# Schematic.net
KiCad netlist of a schematic drawn in EAGLE
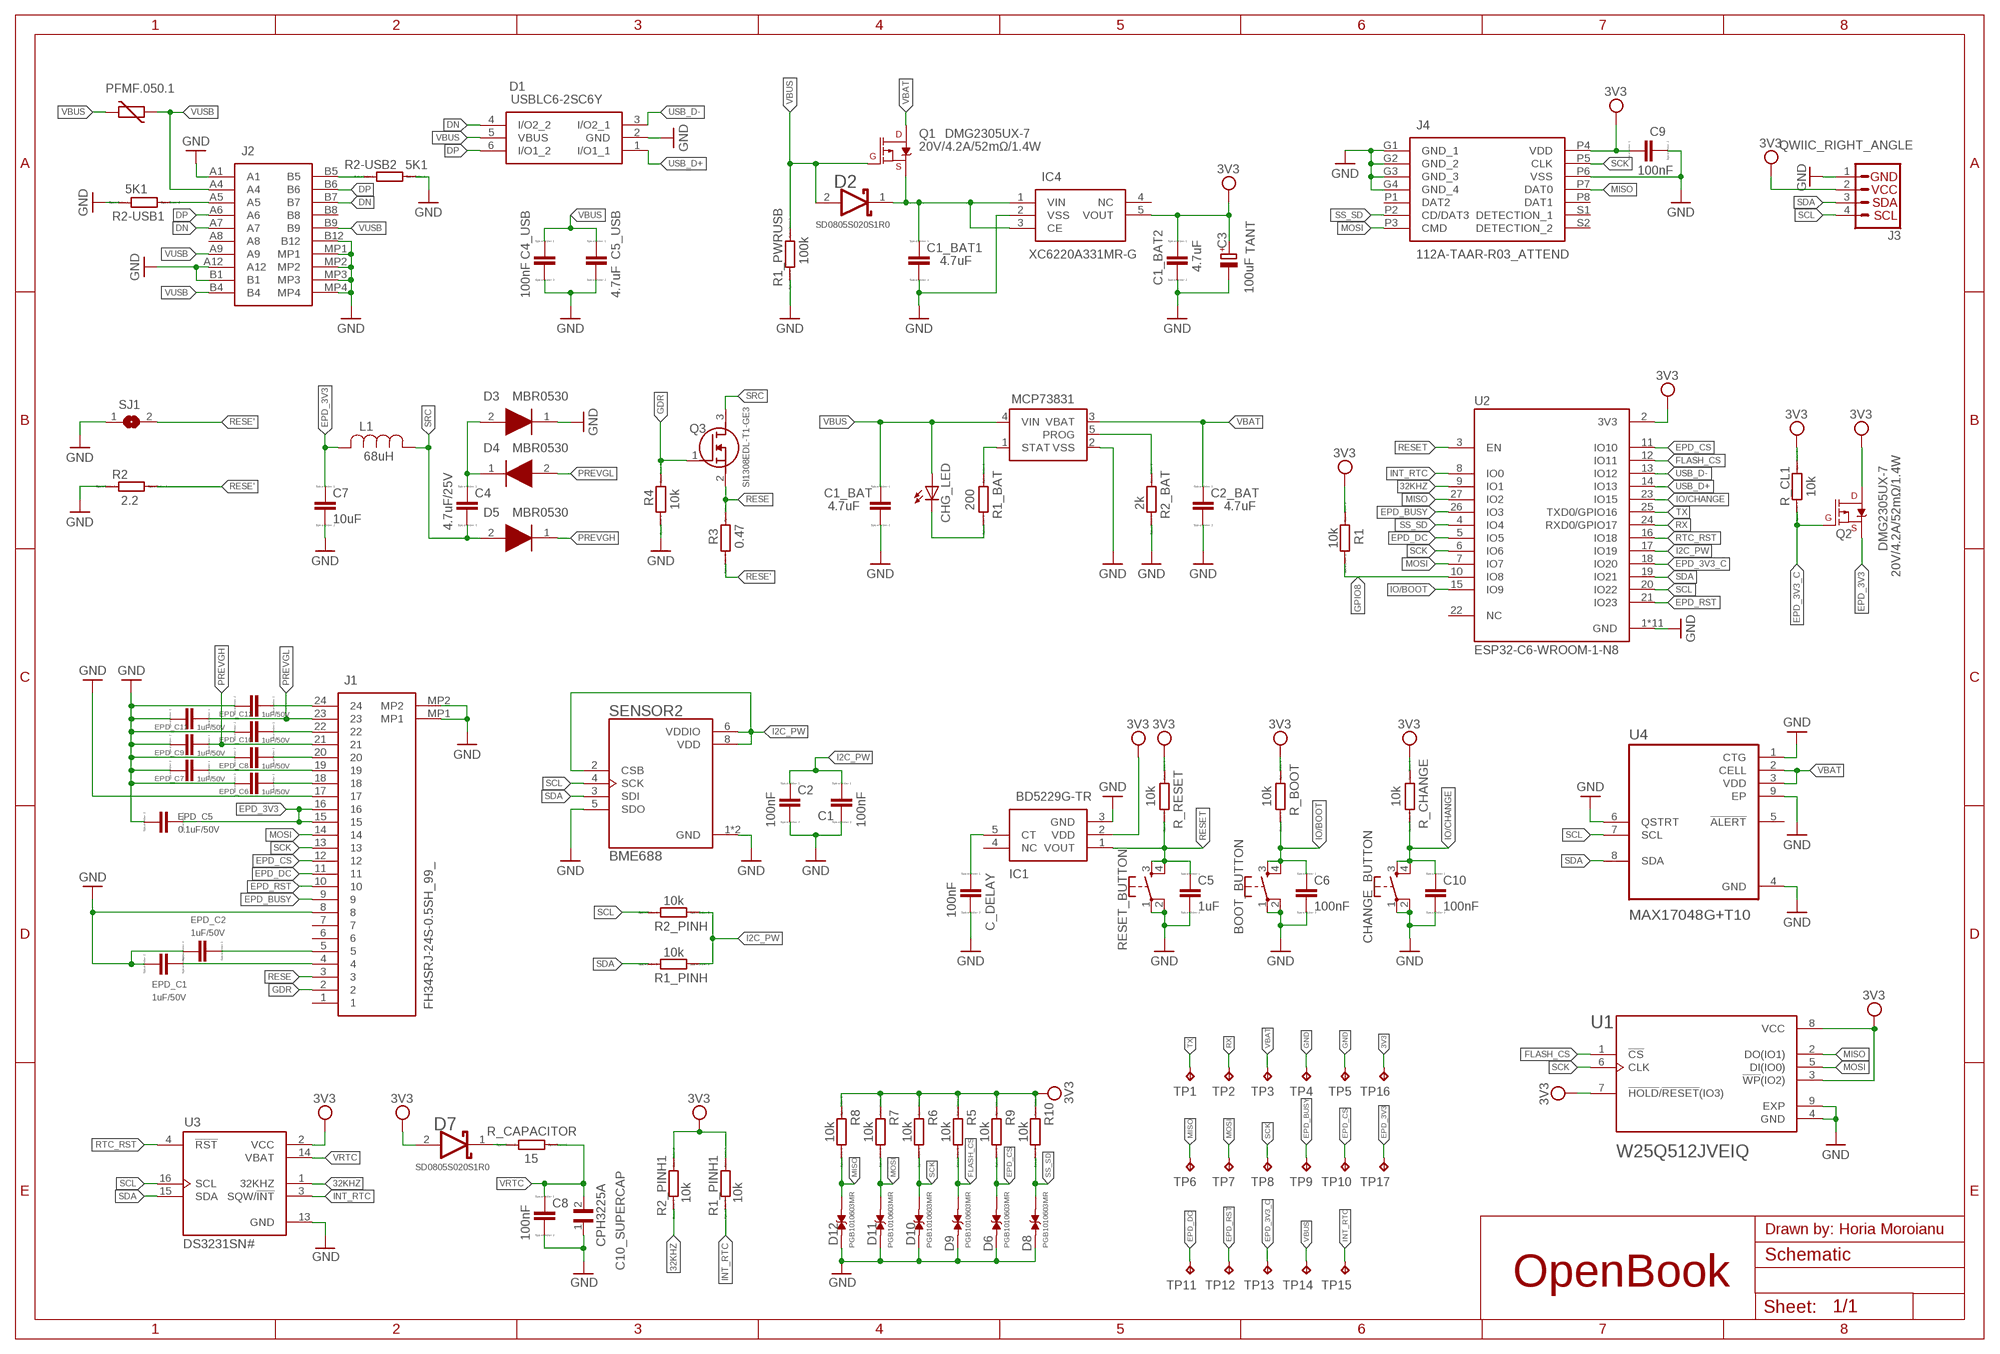
[diagram p0: schematic, sheet 1]

(export (version "E")
  (design (tool "Eeschema 10.0.6"))
  (components
    (comp (ref "BOOT_BUTTON")
      (value "BUTTON_CUSYOMV1")
      (footprint "eagle-import:MYBUTTON")
      (libsource (lib "eagle-import") (part "BUTTON_CUSYOMV1"))
    )
    (comp (ref "C1")
      (value "100nF")
      (footprint "eagle-import:EAGLE-LTSPICE_C0402")
      (libsource (lib "eagle-import") (part "EAGLE-LTSPICE_CC0402"))
    )
    (comp (ref "C1_BAT")
      (value "4.7uF")
      (footprint "eagle-import:EAGLE-LTSPICE_C0402")
      (libsource (lib "eagle-import") (part "EAGLE-LTSPICE_CC0402"))
    )
    (comp (ref "C1_BAT1")
      (value "4.7uF")
      (footprint "eagle-import:EAGLE-LTSPICE_C0402")
      (libsource (lib "eagle-import") (part "EAGLE-LTSPICE_CC0402"))
    )
    (comp (ref "C1_BAT2")
      (value "4.7uF")
      (footprint "eagle-import:EAGLE-LTSPICE_C0402")
      (libsource (lib "eagle-import") (part "EAGLE-LTSPICE_CC0402"))
    )
    (comp (ref "C2")
      (value "100nF")
      (footprint "eagle-import:EAGLE-LTSPICE_C0402")
      (libsource (lib "eagle-import") (part "EAGLE-LTSPICE_CC0402"))
    )
    (comp (ref "C2_BAT")
      (value "4.7uF")
      (footprint "eagle-import:EAGLE-LTSPICE_C0402")
      (libsource (lib "eagle-import") (part "EAGLE-LTSPICE_CC0402"))
    )
    (comp (ref "C3")
      (value "100uF")
      (footprint "eagle-import:RCL_CT3528")
      (libsource (lib "eagle-import") (part "RCL_CPOL-EUCT3528"))
    )
    (comp (ref "C4")
      (value "4.7uF/25V")
      (footprint "eagle-import:EAGLE-LTSPICE_C0402")
      (libsource (lib "eagle-import") (part "EAGLE-LTSPICE_CC0402"))
    )
    (comp (ref "C4_USB")
      (value "100nF")
      (footprint "eagle-import:EAGLE-LTSPICE_C0402")
      (libsource (lib "eagle-import") (part "EAGLE-LTSPICE_CC0402"))
    )
    (comp (ref "C5")
      (value "1uF")
      (footprint "eagle-import:EAGLE-LTSPICE_C0402")
      (libsource (lib "eagle-import") (part "EAGLE-LTSPICE_CC0402"))
    )
    (comp (ref "C5_USB")
      (value "4.7uF")
      (footprint "eagle-import:EAGLE-LTSPICE_C0402")
      (libsource (lib "eagle-import") (part "EAGLE-LTSPICE_CC0402"))
    )
    (comp (ref "C6")
      (value "100nF")
      (footprint "eagle-import:EAGLE-LTSPICE_C0402")
      (libsource (lib "eagle-import") (part "EAGLE-LTSPICE_CC0402"))
    )
    (comp (ref "C7")
      (value "10uF")
      (footprint "eagle-import:EAGLE-LTSPICE_C0402")
      (libsource (lib "eagle-import") (part "EAGLE-LTSPICE_CC0402"))
    )
    (comp (ref "C8")
      (value "100nF")
      (footprint "eagle-import:EAGLE-LTSPICE_C0402")
      (libsource (lib "eagle-import") (part "EAGLE-LTSPICE_CC0402"))
    )
    (comp (ref "C9")
      (value "100nF")
      (footprint "eagle-import:EAGLE-LTSPICE_C0402")
      (libsource (lib "eagle-import") (part "EAGLE-LTSPICE_CC0402"))
    )
    (comp (ref "C10")
      (value "100nF")
      (footprint "eagle-import:EAGLE-LTSPICE_C0402")
      (libsource (lib "eagle-import") (part "EAGLE-LTSPICE_CC0402"))
    )
    (comp (ref "C10_SUPERCAP")
      (value "CPH3225A")
      (footprint "eagle-import:CAPCP3225X100N")
      (fields (field (name "MF") "Seiko Instruments"))
      (libsource (lib "eagle-import") (part "CPH3225A"))
    )
    (comp (ref "CHANGE_BUTTON")
      (value "BUTTON_CUSYOMV1")
      (footprint "eagle-import:MYBUTTON")
      (libsource (lib "eagle-import") (part "BUTTON_CUSYOMV1"))
    )
    (comp (ref "CHG_LED")
      (value "ADAFRUIT_LEDCHIP-LED0603")
      (footprint "eagle-import:ADAFRUIT_CHIP-LED0603")
      (libsource (lib "eagle-import") (part "ADAFRUIT_LEDCHIP-LED0603"))
    )
    (comp (ref "C_DELAY")
      (value "100nF")
      (footprint "eagle-import:EAGLE-LTSPICE_C0402")
      (libsource (lib "eagle-import") (part "EAGLE-LTSPICE_CC0402"))
    )
    (comp (ref "D1")
      (value "USBLC6-2SC6Y")
      (footprint "eagle-import:SOT95P280X145-6N")
      (fields (field (name "MF") "STMicroelectronics"))
      (libsource (lib "eagle-import") (part "USBLC6-2SC6Y"))
    )
    (comp (ref "D2")
      (value "ESP32_WROVER_AVX---SD0805S020S1R0_AVX_SD0805S020S1R0_0_0AVX_SD0805S020S1R0_0_0")
      (footprint "eagle-import:ESP32_WROVER_AVX---SD0805S020S1R0_AVX_SD0805S020S1R0_0")
      (fields
        (field (name "DIGIKEY_PART_NUMBER") "478-7800-1-ND")
        (field (name "MF") "AVX")
        (field (name "MOUSER_PART_NUMBER") "581-SD0805S020S1R0")
      )
      (libsource (lib "eagle-import") (part "ESP32_WROVER_AVX---SD0805S020S1R0_AVX_SD0805S020S1R0_0_0AVX_SD0805S020S1R0_0_0"))
    )
    (comp (ref "D3")
      (value "MBR0530")
      (footprint "eagle-import:SOD3716X135N")
      (fields (field (name "MF") "ON Semiconductor"))
      (libsource (lib "eagle-import") (part "MBR0530"))
    )
    (comp (ref "D4")
      (value "MBR0530")
      (footprint "eagle-import:SOD3716X135N")
      (fields (field (name "MF") "ON Semiconductor"))
      (libsource (lib "eagle-import") (part "MBR0530"))
    )
    (comp (ref "D5")
      (value "MBR0530")
      (footprint "eagle-import:SOD3716X135N")
      (fields (field (name "MF") "ON Semiconductor"))
      (libsource (lib "eagle-import") (part "MBR0530"))
    )
    (comp (ref "D6")
      (value "PGB1010603MR")
      (footprint "eagle-import:DIOC1608X36N")
      (fields (field (name "MF") "Littelfuse Inc."))
      (libsource (lib "eagle-import") (part "PGB1010603MR"))
    )
    (comp (ref "D7")
      (value "ESP32_WROVER_AVX---SD0805S020S1R0_AVX_SD0805S020S1R0_0_0AVX_SD0805S020S1R0_0_0")
      (footprint "eagle-import:ESP32_WROVER_AVX---SD0805S020S1R0_AVX_SD0805S020S1R0_0")
      (fields
        (field (name "DIGIKEY_PART_NUMBER") "478-7800-1-ND")
        (field (name "MF") "AVX")
        (field (name "MOUSER_PART_NUMBER") "581-SD0805S020S1R0")
      )
      (libsource (lib "eagle-import") (part "ESP32_WROVER_AVX---SD0805S020S1R0_AVX_SD0805S020S1R0_0_0AVX_SD0805S020S1R0_0_0"))
    )
    (comp (ref "D8")
      (value "PGB1010603MR")
      (footprint "eagle-import:DIOC1608X36N")
      (fields (field (name "MF") "Littelfuse Inc."))
      (libsource (lib "eagle-import") (part "PGB1010603MR"))
    )
    (comp (ref "D9")
      (value "PGB1010603MR")
      (footprint "eagle-import:DIOC1608X36N")
      (fields (field (name "MF") "Littelfuse Inc."))
      (libsource (lib "eagle-import") (part "PGB1010603MR"))
    )
    (comp (ref "D10")
      (value "PGB1010603MR")
      (footprint "eagle-import:DIOC1608X36N")
      (fields (field (name "MF") "Littelfuse Inc."))
      (libsource (lib "eagle-import") (part "PGB1010603MR"))
    )
    (comp (ref "D11")
      (value "PGB1010603MR")
      (footprint "eagle-import:DIOC1608X36N")
      (fields (field (name "MF") "Littelfuse Inc."))
      (libsource (lib "eagle-import") (part "PGB1010603MR"))
    )
    (comp (ref "D12")
      (value "PGB1010603MR")
      (footprint "eagle-import:DIOC1608X36N")
      (fields (field (name "MF") "Littelfuse Inc."))
      (libsource (lib "eagle-import") (part "PGB1010603MR"))
    )
    (comp (ref "EPD_C1")
      (value "1uF/50V")
      (footprint "eagle-import:EAGLE-LTSPICE_C0402")
      (libsource (lib "eagle-import") (part "EAGLE-LTSPICE_CC0402"))
    )
    (comp (ref "EPD_C2")
      (value "1uF/50V")
      (footprint "eagle-import:EAGLE-LTSPICE_C0402")
      (libsource (lib "eagle-import") (part "EAGLE-LTSPICE_CC0402"))
    )
    (comp (ref "EPD_C5")
      (value "0.1uF/50V")
      (footprint "eagle-import:EAGLE-LTSPICE_C0402")
      (libsource (lib "eagle-import") (part "EAGLE-LTSPICE_CC0402"))
    )
    (comp (ref "EPD_C6")
      (value "1uF/50V")
      (footprint "eagle-import:EAGLE-LTSPICE_C0402")
      (libsource (lib "eagle-import") (part "EAGLE-LTSPICE_CC0402"))
    )
    (comp (ref "EPD_C7")
      (value "1uF/50V")
      (footprint "eagle-import:EAGLE-LTSPICE_C0402")
      (libsource (lib "eagle-import") (part "EAGLE-LTSPICE_CC0402"))
    )
    (comp (ref "EPD_C8")
      (value "1uF/50V")
      (footprint "eagle-import:EAGLE-LTSPICE_C0402")
      (libsource (lib "eagle-import") (part "EAGLE-LTSPICE_CC0402"))
    )
    (comp (ref "EPD_C9")
      (value "1uF/50V")
      (footprint "eagle-import:EAGLE-LTSPICE_C0402")
      (libsource (lib "eagle-import") (part "EAGLE-LTSPICE_CC0402"))
    )
    (comp (ref "EPD_C10")
      (value "1uF/50V")
      (footprint "eagle-import:EAGLE-LTSPICE_C0402")
      (libsource (lib "eagle-import") (part "EAGLE-LTSPICE_CC0402"))
    )
    (comp (ref "EPD_C11")
      (value "1uF/50V")
      (footprint "eagle-import:EAGLE-LTSPICE_C0402")
      (libsource (lib "eagle-import") (part "EAGLE-LTSPICE_CC0402"))
    )
    (comp (ref "EPD_C12")
      (value "1uF/50V")
      (footprint "eagle-import:EAGLE-LTSPICE_C0402")
      (libsource (lib "eagle-import") (part "EAGLE-LTSPICE_CC0402"))
    )
    (comp (ref "IC1")
      (value "BD5229G-TR")
      (footprint "eagle-import:SOT95P280X125-5N")
      (fields (field (name "MOUSER_PART_NUMBER") "755-BD5229G-TR"))
      (libsource (lib "eagle-import") (part "BD5229G-TR"))
    )
    (comp (ref "IC4")
      (value "XC6220A331MR-G")
      (footprint "eagle-import:SOT95P280X120-5N")
      (fields (field (name "MOUSER_PART_NUMBER") "865-XC6220A331MR-G"))
      (libsource (lib "eagle-import") (part "XC6220A331MR-G"))
    )
    (comp (ref "J1")
      (value "FH34SRJ-24S-0.5SH_99_")
      (footprint "eagle-import:FH34SRJ24S05SH99")
      (fields
        (field (name "MANUFACTURER_PART_NUMBER") "FH34SRJ-24S-0.5SH(99)")
        (field (name "MOUSER_PART_NUMBER") "798-FH34SRJ24S05SH99")
      )
      (libsource (lib "eagle-import") (part "FH34SRJ-24S-0.5SH_99_"))
    )
    (comp (ref "J2")
      (value "SAMACSYS_PARTS_USB4110-GF-A")
      (footprint "eagle-import:SAMACSYS_PARTS_USB4110GFA")
      (fields
        (field (name "MANUFACTURER_PART_NUMBER") "USB4110-GF-A")
        (field (name "MOUSER_PART_NUMBER") "640-USB4110-GF-A")
      )
      (libsource (lib "eagle-import") (part "SAMACSYS_PARTS_USB4110-GF-A"))
    )
    (comp (ref "J3")
      (value "QWIIC_RIGHT_ANGLE")
      (footprint "eagle-import:JST04_1MM_RA")
      (libsource (lib "eagle-import") (part "QWIIC_CONNECTORJS-1MM"))
    )
    (comp (ref "J4")
      (value "112A-TAAR-R03_ATTEND")
      (footprint "eagle-import:112ATAARR03ATTEND")
      (fields (field (name "MANUFACTURER_PART_NUMBER") "112A-TAAR-R03 ATTEND"))
      (libsource (lib "eagle-import") (part "112A-TAAR-R03_ATTEND"))
    )
    (comp (ref "L1")
      (value "744043680IND_4828-WE-TPC_WRE")
      (footprint "eagle-import:IND_4828-WE-TPC_WRE")
      (fields
        (field (name "MANUFACTURER_PART_NUMBER") "744043680")
        (field (name "VAL") "68uH")
        (field (name "COPYRIGHT") "Copyright (C) 2024 Ultra Librarian. All rights reserved.")
      )
      (libsource (lib "eagle-import") (part "744043680IND_4828-WE-TPC_WRE"))
    )
    (comp (ref "PFMF.050.1")
      (value "ESP32C6_VARISTORCN1812")
      (footprint "eagle-import:ESP32C6_VARISTOR_CT_CN1812")
      (libsource (lib "eagle-import") (part "ESP32C6_VARISTORCN1812"))
    )
    (comp (ref "Q1")
      (value "20V/4.2A/52mΩ/1.4W")
      (footprint "eagle-import:ESP32_WROVER_SPARKFUN-DISCRETESEMI_SOT23-3")
      (libsource (lib "eagle-import") (part "ESP32_WROVER_SPARKFUN-DISCRETESEMI_MOSFET_PCH-DMG2305UX-7"))
    )
    (comp (ref "Q2")
      (value "20V/4.2A/52mΩ/1.4W")
      (footprint "eagle-import:ESP32_WROVER_SPARKFUN-DISCRETESEMI_SOT23-3")
      (libsource (lib "eagle-import") (part "ESP32_WROVER_SPARKFUN-DISCRETESEMI_MOSFET_PCH-DMG2305UX-7"))
    )
    (comp (ref "Q3")
      (value "SI1308EDL-T1-GE3")
      (footprint "eagle-import:SOT65P210X110-3N")
      (fields (field (name "MF") "Vishay Siliconix"))
      (libsource (lib "eagle-import") (part "SI1308EDL-T1-GE3"))
    )
    (comp (ref "R1")
      (value "10k")
      (footprint "eagle-import:ESP32_WROVER_EAGLE-LTSPICE_R0402")
      (libsource (lib "eagle-import") (part "ESP32_WROVER_EAGLE-LTSPICE_RR0402"))
    )
    (comp (ref "R1_BAT")
      (value "200")
      (footprint "eagle-import:ESP32_WROVER_EAGLE-LTSPICE_R0402")
      (libsource (lib "eagle-import") (part "ESP32_WROVER_EAGLE-LTSPICE_RR0402"))
    )
    (comp (ref "R1_PINH")
      (value "10k")
      (footprint "eagle-import:ESP32_WROVER_EAGLE-LTSPICE_R0402")
      (libsource (lib "eagle-import") (part "ESP32_WROVER_EAGLE-LTSPICE_RR0402"))
    )
    (comp (ref "R1_PINH1")
      (value "10k")
      (footprint "eagle-import:ESP32_WROVER_EAGLE-LTSPICE_R0402")
      (libsource (lib "eagle-import") (part "ESP32_WROVER_EAGLE-LTSPICE_RR0402"))
    )
    (comp (ref "R1_PWRUSB")
      (value "100k")
      (footprint "eagle-import:ESP32_WROVER_EAGLE-LTSPICE_R0402")
      (libsource (lib "eagle-import") (part "ESP32_WROVER_EAGLE-LTSPICE_RR0402"))
    )
    (comp (ref "R2")
      (value "2.2")
      (footprint "eagle-import:ESP32_WROVER_EAGLE-LTSPICE_R0402")
      (libsource (lib "eagle-import") (part "ESP32_WROVER_EAGLE-LTSPICE_RR0402"))
    )
    (comp (ref "R2-USB1")
      (value "5K1")
      (footprint "eagle-import:ESP32_WROVER_EAGLE-LTSPICE_R0402")
      (libsource (lib "eagle-import") (part "ESP32_WROVER_EAGLE-LTSPICE_RR0402"))
    )
    (comp (ref "R2-USB2")
      (value "5K1")
      (footprint "eagle-import:ESP32_WROVER_EAGLE-LTSPICE_R0402")
      (libsource (lib "eagle-import") (part "ESP32_WROVER_EAGLE-LTSPICE_RR0402"))
    )
    (comp (ref "R2_BAT")
      (value "2k")
      (footprint "eagle-import:ESP32_WROVER_EAGLE-LTSPICE_R0402")
      (libsource (lib "eagle-import") (part "ESP32_WROVER_EAGLE-LTSPICE_RR0402"))
    )
    (comp (ref "R2_PINH")
      (value "10k")
      (footprint "eagle-import:ESP32_WROVER_EAGLE-LTSPICE_R0402")
      (libsource (lib "eagle-import") (part "ESP32_WROVER_EAGLE-LTSPICE_RR0402"))
    )
    (comp (ref "R2_PINH1")
      (value "10k")
      (footprint "eagle-import:ESP32_WROVER_EAGLE-LTSPICE_R0402")
      (libsource (lib "eagle-import") (part "ESP32_WROVER_EAGLE-LTSPICE_RR0402"))
    )
    (comp (ref "R3")
      (value "0.47")
      (footprint "eagle-import:ESP32_WROVER_EAGLE-LTSPICE_R0402")
      (libsource (lib "eagle-import") (part "ESP32_WROVER_EAGLE-LTSPICE_RR0402"))
    )
    (comp (ref "R4")
      (value "10k")
      (footprint "eagle-import:ESP32_WROVER_EAGLE-LTSPICE_R0402")
      (libsource (lib "eagle-import") (part "ESP32_WROVER_EAGLE-LTSPICE_RR0402"))
    )
    (comp (ref "R5")
      (value "10k")
      (footprint "eagle-import:ESP32_WROVER_EAGLE-LTSPICE_R0402")
      (libsource (lib "eagle-import") (part "ESP32_WROVER_EAGLE-LTSPICE_RR0402"))
    )
    (comp (ref "R6")
      (value "10k")
      (footprint "eagle-import:ESP32_WROVER_EAGLE-LTSPICE_R0402")
      (libsource (lib "eagle-import") (part "ESP32_WROVER_EAGLE-LTSPICE_RR0402"))
    )
    (comp (ref "R7")
      (value "10k")
      (footprint "eagle-import:ESP32_WROVER_EAGLE-LTSPICE_R0402")
      (libsource (lib "eagle-import") (part "ESP32_WROVER_EAGLE-LTSPICE_RR0402"))
    )
    (comp (ref "R8")
      (value "10k")
      (footprint "eagle-import:ESP32_WROVER_EAGLE-LTSPICE_R0402")
      (libsource (lib "eagle-import") (part "ESP32_WROVER_EAGLE-LTSPICE_RR0402"))
    )
    (comp (ref "R9")
      (value "10k")
      (footprint "eagle-import:ESP32_WROVER_EAGLE-LTSPICE_R0402")
      (libsource (lib "eagle-import") (part "ESP32_WROVER_EAGLE-LTSPICE_RR0402"))
    )
    (comp (ref "R10")
      (value "10k")
      (footprint "eagle-import:ESP32_WROVER_EAGLE-LTSPICE_R0402")
      (libsource (lib "eagle-import") (part "ESP32_WROVER_EAGLE-LTSPICE_RR0402"))
    )
    (comp (ref "RESET_BUTTON")
      (value "BUTTON_CUSYOMV1")
      (footprint "eagle-import:MYBUTTON")
      (libsource (lib "eagle-import") (part "BUTTON_CUSYOMV1"))
    )
    (comp (ref "R_BOOT")
      (value "10k")
      (footprint "eagle-import:ESP32_WROVER_EAGLE-LTSPICE_R0402")
      (libsource (lib "eagle-import") (part "ESP32_WROVER_EAGLE-LTSPICE_RR0402"))
    )
    (comp (ref "R_CAPACITOR")
      (value "15")
      (footprint "eagle-import:ESP32_WROVER_EAGLE-LTSPICE_R0402")
      (libsource (lib "eagle-import") (part "ESP32_WROVER_EAGLE-LTSPICE_RR0402"))
    )
    (comp (ref "R_CHANGE")
      (value "10k")
      (footprint "eagle-import:ESP32_WROVER_EAGLE-LTSPICE_R0402")
      (libsource (lib "eagle-import") (part "ESP32_WROVER_EAGLE-LTSPICE_RR0402"))
    )
    (comp (ref "R_CL1")
      (value "10k")
      (footprint "eagle-import:ESP32_WROVER_EAGLE-LTSPICE_R0402")
      (libsource (lib "eagle-import") (part "ESP32_WROVER_EAGLE-LTSPICE_RR0402"))
    )
    (comp (ref "R_RESET")
      (value "10k")
      (footprint "eagle-import:ESP32_WROVER_EAGLE-LTSPICE_R0402")
      (libsource (lib "eagle-import") (part "ESP32_WROVER_EAGLE-LTSPICE_RR0402"))
    )
    (comp (ref "SENSOR2")
      (value "ESP32_WROVER_BME680_BME680")
      (footprint "eagle-import:ESP32_WROVER_BME680_PSON80P300X300X100-8N")
      (fields (field (name "MF") "Bosch Sensortec") (field (name "MP") "BME680"))
      (libsource (lib "eagle-import") (part "ESP32_WROVER_BME680_BME680"))
    )
    (comp (ref "SJ1") (value "SJ") (footprint "eagle-import:SJ") (libsource (lib "eagle-import") (part "SJ")))
    (comp (ref "TP1")
      (value "TPTP20R")
      (footprint "eagle-import:TP20R")
      (libsource (lib "eagle-import") (part "TPTP20R"))
    )
    (comp (ref "TP2")
      (value "TPTP20R")
      (footprint "eagle-import:TP20R")
      (libsource (lib "eagle-import") (part "TPTP20R"))
    )
    (comp (ref "TP3")
      (value "TPTP20R")
      (footprint "eagle-import:TP20R")
      (libsource (lib "eagle-import") (part "TPTP20R"))
    )
    (comp (ref "TP4")
      (value "TPTP20R")
      (footprint "eagle-import:TP20R")
      (libsource (lib "eagle-import") (part "TPTP20R"))
    )
    (comp (ref "TP5")
      (value "TPTP20R")
      (footprint "eagle-import:TP20R")
      (libsource (lib "eagle-import") (part "TPTP20R"))
    )
    (comp (ref "TP6")
      (value "TPTP20R")
      (footprint "eagle-import:TP20R")
      (libsource (lib "eagle-import") (part "TPTP20R"))
    )
    (comp (ref "TP7")
      (value "TPTP20R")
      (footprint "eagle-import:TP20R")
      (libsource (lib "eagle-import") (part "TPTP20R"))
    )
    (comp (ref "TP8")
      (value "TPTP20R")
      (footprint "eagle-import:TP20R")
      (libsource (lib "eagle-import") (part "TPTP20R"))
    )
    (comp (ref "TP9")
      (value "TPTP20R")
      (footprint "eagle-import:TP20R")
      (libsource (lib "eagle-import") (part "TPTP20R"))
    )
    (comp (ref "TP10")
      (value "TPTP20R")
      (footprint "eagle-import:TP20R")
      (libsource (lib "eagle-import") (part "TPTP20R"))
    )
    (comp (ref "TP11")
      (value "TPTP20R")
      (footprint "eagle-import:TP20R")
      (libsource (lib "eagle-import") (part "TPTP20R"))
    )
    (comp (ref "TP12")
      (value "TPTP20R")
      (footprint "eagle-import:TP20R")
      (libsource (lib "eagle-import") (part "TPTP20R"))
    )
    (comp (ref "TP13")
      (value "TPTP20R")
      (footprint "eagle-import:TP20R")
      (libsource (lib "eagle-import") (part "TPTP20R"))
    )
    (comp (ref "TP14")
      (value "TPTP20R")
      (footprint "eagle-import:TP20R")
      (libsource (lib "eagle-import") (part "TPTP20R"))
    )
    (comp (ref "TP15")
      (value "TPTP20R")
      (footprint "eagle-import:TP20R")
      (libsource (lib "eagle-import") (part "TPTP20R"))
    )
    (comp (ref "TP16")
      (value "TPTP20R")
      (footprint "eagle-import:TP20R")
      (libsource (lib "eagle-import") (part "TPTP20R"))
    )
    (comp (ref "TP17")
      (value "TPTP20R")
      (footprint "eagle-import:TP20R")
      (libsource (lib "eagle-import") (part "TPTP20R"))
    )
    (comp (ref "U1")
      (value "W25Q512JVEIQ")
      (footprint "eagle-import:SON127P600X800X80-9N")
      (fields (field (name "MF") "Winbond Electronics"))
      (libsource (lib "eagle-import") (part "W25Q512JVEIQ"))
    )
    (comp (ref "U2")
      (value "ESP32-C6-WROOM-1-N8")
      (footprint "eagle-import:XCVR_ESP32-C6-WROOM-1-N8")
      (fields (field (name "MF") "Espressif Systems"))
      (libsource (lib "eagle-import") (part "ESP32-C6-WROOM-1-N8"))
    )
    (comp (ref "U3")
      (value "DS3231SN#")
      (footprint "eagle-import:SOIC127P1032X265-16N")
      (fields (field (name "MF") "Analog Devices"))
      (libsource (lib "eagle-import") (part "DS3231SN#"))
    )
    (comp (ref "U4")
      (value "MAX17048G+T10")
      (footprint "eagle-import:SON50P200X200X80-9N")
      (fields (field (name "MF") "Analog Devices"))
      (libsource (lib "eagle-import") (part "MAX17048G+T10"))
    )
    (comp (ref "U5")
      (value "ESP32_WROVER_SPARKFUN-IC-POWER_MCP73831")
      (footprint "eagle-import:ESP32_WROVER_SPARKFUN-IC-POWER_SOT23-5")
      (libsource (lib "eagle-import") (part "ESP32_WROVER_SPARKFUN-IC-POWER_MCP73831"))
    )
  )
  (nets
    (net (code "1") (name "3V3") (class "Default")
      (node (ref "C1_BAT2") (pin "1") (pinfunction "1_1") (pintype "passive"))
      (node (ref "C3") (pin "+") (pinfunction "+_+") (pintype "passive"))
      (node (ref "C9") (pin "1") (pinfunction "1_1") (pintype "passive"))
      (node (ref "D7") (pin "2") (pinfunction "ANODE_2") (pintype "bidirectional"))
      (node (ref "IC1") (pin "2") (pinfunction "VDD_2") (pintype "bidirectional"))
      (node (ref "IC4") (pin "5") (pinfunction "VOUT_5") (pintype "bidirectional"))
      (node (ref "J3") (pin "2") (pinfunction "2_2") (pintype "power_in"))
      (node (ref "J4") (pin "P4") (pinfunction "VDD_P4") (pintype "bidirectional"))
      (node (ref "Q2") (pin "3") (pinfunction "D_3") (pintype "bidirectional"))
      (node (ref "R1") (pin "2") (pinfunction "2_2") (pintype "passive"))
      (node (ref "R10") (pin "2") (pinfunction "2_2") (pintype "passive"))
      (node (ref "R1_PINH1") (pin "2") (pinfunction "2_2") (pintype "passive"))
      (node (ref "R2_PINH1") (pin "2") (pinfunction "2_2") (pintype "passive"))
      (node (ref "R5") (pin "2") (pinfunction "2_2") (pintype "passive"))
      (node (ref "R6") (pin "2") (pinfunction "2_2") (pintype "passive"))
      (node (ref "R7") (pin "2") (pinfunction "2_2") (pintype "passive"))
      (node (ref "R8") (pin "2") (pinfunction "2_2") (pintype "passive"))
      (node (ref "R9") (pin "2") (pinfunction "2_2") (pintype "passive"))
      (node (ref "R_BOOT") (pin "1") (pinfunction "1_1") (pintype "passive"))
      (node (ref "R_CHANGE") (pin "1") (pinfunction "1_1") (pintype "passive"))
      (node (ref "R_CL1") (pin "2") (pinfunction "2_2") (pintype "passive"))
      (node (ref "R_RESET") (pin "1") (pinfunction "1_1") (pintype "passive"))
      (node (ref "TP16") (pin "TP") (pinfunction "TP_TP") (pintype "input"))
      (node (ref "U1") (pin "3") (pinfunction "~{WP}(IO2)_3") (pintype "bidirectional"))
      (node (ref "U1") (pin "7") (pinfunction "~{HOLD}/~{RESET}(IO3)_7") (pintype "bidirectional"))
      (node (ref "U1") (pin "8") (pinfunction "VCC_8") (pintype "power_in"))
      (node (ref "U2") (pin "2") (pinfunction "3V3_2") (pintype "power_in"))
      (node (ref "U3") (pin "2") (pinfunction "VCC_2") (pintype "power_in"))
    )
    (net (code "2") (name "32KHZ") (class "Default")
      (node (ref "R2_PINH1") (pin "1") (pinfunction "1_1") (pintype "passive"))
      (node (ref "U2") (pin "9") (pinfunction "IO1_9") (pintype "bidirectional"))
      (node (ref "U3") (pin "1") (pinfunction "32KHZ_1") (pintype "output"))
    )
    (net (code "3") (name "DN") (class "Default")
      (node (ref "D1") (pin "4") (pinfunction "I/O2_2_4") (pintype "bidirectional"))
      (node (ref "J2") (pin "A7") (pinfunction "A7_A7") (pintype "bidirectional"))
      (node (ref "J2") (pin "B7") (pinfunction "B7_B7") (pintype "bidirectional"))
    )
    (net (code "4") (name "DP") (class "Default")
      (node (ref "D1") (pin "6") (pinfunction "I/O1_2_6") (pintype "bidirectional"))
      (node (ref "J2") (pin "A6") (pinfunction "A6_A6") (pintype "bidirectional"))
      (node (ref "J2") (pin "B6") (pinfunction "B6_B6") (pintype "bidirectional"))
    )
    (net (code "5") (name "EPD_3V3") (class "Default")
      (node (ref "C7") (pin "1") (pinfunction "1_1") (pintype "passive"))
      (node (ref "EPD_C5") (pin "1") (pinfunction "1_1") (pintype "passive"))
      (node (ref "J1") (pin "15") (pinfunction "15_15") (pintype "bidirectional"))
      (node (ref "J1") (pin "16") (pinfunction "16_16") (pintype "bidirectional"))
      (node (ref "L1") (pin "2") (pinfunction "2_2") (pintype "passive"))
      (node (ref "Q2") (pin "2") (pinfunction "S_2") (pintype "bidirectional"))
      (node (ref "TP17") (pin "TP") (pinfunction "TP_TP") (pintype "input"))
    )
    (net (code "6") (name "EPD_3V3_C") (class "Default")
      (node (ref "Q2") (pin "1") (pinfunction "G_1") (pintype "bidirectional"))
      (node (ref "R_CL1") (pin "1") (pinfunction "1_1") (pintype "passive"))
      (node (ref "TP13") (pin "TP") (pinfunction "TP_TP") (pintype "input"))
      (node (ref "U2") (pin "18") (pinfunction "IO20_18") (pintype "bidirectional"))
    )
    (net (code "7") (name "EPD_BUSY") (class "Default")
      (node (ref "J1") (pin "9") (pinfunction "9_9") (pintype "bidirectional"))
      (node (ref "TP9") (pin "TP") (pinfunction "TP_TP") (pintype "input"))
      (node (ref "U2") (pin "26") (pinfunction "IO3_26") (pintype "bidirectional"))
    )
    (net (code "8") (name "EPD_CS") (class "Default")
      (node (ref "D6") (pin "2") (pinfunction "2_2") (pintype "passive"))
      (node (ref "J1") (pin "12") (pinfunction "12_12") (pintype "bidirectional"))
      (node (ref "R9") (pin "1") (pinfunction "1_1") (pintype "passive"))
      (node (ref "TP10") (pin "TP") (pinfunction "TP_TP") (pintype "input"))
      (node (ref "U2") (pin "11") (pinfunction "IO10_11") (pintype "bidirectional"))
    )
    (net (code "9") (name "EPD_DC") (class "Default")
      (node (ref "J1") (pin "11") (pinfunction "11_11") (pintype "bidirectional"))
      (node (ref "TP11") (pin "TP") (pinfunction "TP_TP") (pintype "input"))
      (node (ref "U2") (pin "5") (pinfunction "IO5_5") (pintype "bidirectional"))
    )
    (net (code "10") (name "EPD_RST") (class "Default")
      (node (ref "J1") (pin "10") (pinfunction "10_10") (pintype "bidirectional"))
      (node (ref "TP12") (pin "TP") (pinfunction "TP_TP") (pintype "input"))
      (node (ref "U2") (pin "21") (pinfunction "IO23_21") (pintype "bidirectional"))
    )
    (net (code "11") (name "FLASH_CS") (class "Default")
      (node (ref "D9") (pin "2") (pinfunction "2_2") (pintype "passive"))
      (node (ref "R5") (pin "1") (pinfunction "1_1") (pintype "passive"))
      (node (ref "U1") (pin "1") (pinfunction "~{CS}_1") (pintype "input"))
      (node (ref "U2") (pin "12") (pinfunction "IO11_12") (pintype "bidirectional"))
    )
    (net (code "12") (name "GDR") (class "Default")
      (node (ref "J1") (pin "2") (pinfunction "2_2") (pintype "bidirectional"))
      (node (ref "Q3") (pin "1") (pinfunction "G_1") (pintype "bidirectional"))
      (node (ref "R4") (pin "2") (pinfunction "2_2") (pintype "passive"))
    )
    (net (code "13") (name "GND") (class "Default")
      (node (ref "BOOT_BUTTON") (pin "1") (pinfunction "1_1") (pintype "passive"))
      (node (ref "BOOT_BUTTON") (pin "2") (pinfunction "2_2") (pintype "passive"))
      (node (ref "C1") (pin "2") (pinfunction "2_2") (pintype "passive"))
      (node (ref "C10") (pin "2") (pinfunction "2_2") (pintype "passive"))
      (node (ref "C10_SUPERCAP") (pin "1") (pinfunction "1_1") (pintype "passive"))
      (node (ref "C1_BAT") (pin "2") (pinfunction "2_2") (pintype "passive"))
      (node (ref "C1_BAT1") (pin "2") (pinfunction "2_2") (pintype "passive"))
      (node (ref "C1_BAT2") (pin "2") (pinfunction "2_2") (pintype "passive"))
      (node (ref "C2") (pin "2") (pinfunction "2_2") (pintype "passive"))
      (node (ref "C2_BAT") (pin "2") (pinfunction "2_2") (pintype "passive"))
      (node (ref "C3") (pin "-") (pinfunction "-_-") (pintype "passive"))
      (node (ref "C4_USB") (pin "2") (pinfunction "2_2") (pintype "passive"))
      (node (ref "C5") (pin "2") (pinfunction "2_2") (pintype "passive"))
      (node (ref "C5_USB") (pin "2") (pinfunction "2_2") (pintype "passive"))
      (node (ref "C6") (pin "2") (pinfunction "2_2") (pintype "passive"))
      (node (ref "C7") (pin "2") (pinfunction "2_2") (pintype "passive"))
      (node (ref "C8") (pin "2") (pinfunction "2_2") (pintype "passive"))
      (node (ref "C9") (pin "2") (pinfunction "2_2") (pintype "passive"))
      (node (ref "CHANGE_BUTTON") (pin "1") (pinfunction "1_1") (pintype "passive"))
      (node (ref "CHANGE_BUTTON") (pin "2") (pinfunction "2_2") (pintype "passive"))
      (node (ref "C_DELAY") (pin "2") (pinfunction "2_2") (pintype "passive"))
      (node (ref "D1") (pin "2") (pinfunction "GND_2") (pintype "bidirectional"))
      (node (ref "D10") (pin "1") (pinfunction "1_1") (pintype "passive"))
      (node (ref "D11") (pin "1") (pinfunction "1_1") (pintype "passive"))
      (node (ref "D12") (pin "1") (pinfunction "1_1") (pintype "passive"))
      (node (ref "D3") (pin "1") (pinfunction "K_1") (pintype "bidirectional"))
      (node (ref "D6") (pin "1") (pinfunction "1_1") (pintype "passive"))
      (node (ref "D8") (pin "1") (pinfunction "1_1") (pintype "passive"))
      (node (ref "D9") (pin "1") (pinfunction "1_1") (pintype "passive"))
      (node (ref "EPD_C1") (pin "2") (pinfunction "2_2") (pintype "passive"))
      (node (ref "EPD_C10") (pin "2") (pinfunction "2_2") (pintype "passive"))
      (node (ref "EPD_C11") (pin "2") (pinfunction "2_2") (pintype "passive"))
      (node (ref "EPD_C12") (pin "2") (pinfunction "2_2") (pintype "passive"))
      (node (ref "EPD_C2") (pin "2") (pinfunction "2_2") (pintype "passive"))
      (node (ref "EPD_C5") (pin "2") (pinfunction "2_2") (pintype "passive"))
      (node (ref "EPD_C6") (pin "2") (pinfunction "2_2") (pintype "passive"))
      (node (ref "EPD_C7") (pin "2") (pinfunction "2_2") (pintype "passive"))
      (node (ref "EPD_C8") (pin "2") (pinfunction "2_2") (pintype "passive"))
      (node (ref "EPD_C9") (pin "2") (pinfunction "2_2") (pintype "passive"))
      (node (ref "IC1") (pin "3") (pinfunction "GND_3") (pintype "bidirectional"))
      (node (ref "IC4") (pin "2") (pinfunction "VSS_2") (pintype "bidirectional"))
      (node (ref "J1") (pin "17") (pinfunction "17_17") (pintype "bidirectional"))
      (node (ref "J1") (pin "8") (pinfunction "8_8") (pintype "bidirectional"))
      (node (ref "J1") (pin "MP1") (pinfunction "MP1_MP1") (pintype "bidirectional"))
      (node (ref "J1") (pin "MP2") (pinfunction "MP2_MP2") (pintype "bidirectional"))
      (node (ref "J2") (pin "A1") (pinfunction "A1_A1") (pintype "bidirectional"))
      (node (ref "J2") (pin "A12") (pinfunction "A12_A12") (pintype "bidirectional"))
      (node (ref "J2") (pin "B1") (pinfunction "B1_B1") (pintype "bidirectional"))
      (node (ref "J2") (pin "B12") (pinfunction "B12_B12") (pintype "bidirectional"))
      (node (ref "J2") (pin "MP1") (pinfunction "MP1_MP1") (pintype "bidirectional"))
      (node (ref "J2") (pin "MP2") (pinfunction "MP2_MP2") (pintype "bidirectional"))
      (node (ref "J2") (pin "MP3") (pinfunction "MP3_MP3") (pintype "bidirectional"))
      (node (ref "J2") (pin "MP4") (pinfunction "MP4_MP4") (pintype "bidirectional"))
      (node (ref "J3") (pin "1") (pinfunction "1_1") (pintype "power_in"))
      (node (ref "J4") (pin "G1") (pinfunction "GND_1_G1") (pintype "bidirectional"))
      (node (ref "J4") (pin "G2") (pinfunction "GND_2_G2") (pintype "bidirectional"))
      (node (ref "J4") (pin "G3") (pinfunction "GND_3_G3") (pintype "bidirectional"))
      (node (ref "J4") (pin "G4") (pinfunction "GND_4_G4") (pintype "bidirectional"))
      (node (ref "J4") (pin "P6") (pinfunction "VSS_P6") (pintype "bidirectional"))
      (node (ref "R1_PWRUSB") (pin "1") (pinfunction "1_1") (pintype "passive"))
      (node (ref "R2") (pin "1") (pinfunction "1_1") (pintype "passive"))
      (node (ref "R2-USB1") (pin "1") (pinfunction "1_1") (pintype "passive"))
      (node (ref "R2-USB2") (pin "2") (pinfunction "2_2") (pintype "passive"))
      (node (ref "R2_BAT") (pin "1") (pinfunction "1_1") (pintype "passive"))
      (node (ref "R4") (pin "1") (pinfunction "1_1") (pintype "passive"))
      (node (ref "RESET_BUTTON") (pin "1") (pinfunction "1_1") (pintype "passive"))
      (node (ref "RESET_BUTTON") (pin "2") (pinfunction "2_2") (pintype "passive"))
      (node (ref "SENSOR2") (pin "1") (pinfunction "GND_1") (pintype "power_in"))
      (node (ref "SENSOR2") (pin "5") (pinfunction "SDO_5") (pintype "bidirectional"))
      (node (ref "SENSOR2") (pin "7") (pinfunction "GND_7") (pintype "power_in"))
      (node (ref "SJ1") (pin "1") (pinfunction "1_1") (pintype "passive"))
      (node (ref "TP4") (pin "TP") (pinfunction "TP_TP") (pintype "input"))
      (node (ref "TP5") (pin "TP") (pinfunction "TP_TP") (pintype "input"))
      (node (ref "U1") (pin "4") (pinfunction "GND_4") (pintype "power_in"))
      (node (ref "U1") (pin "9") (pinfunction "EXP_9") (pintype "passive"))
      (node (ref "U2") (pin "1") (pinfunction "GND_1") (pintype "power_in"))
      (node (ref "U2") (pin "28") (pinfunction "GND_28") (pintype "power_in"))
      (node (ref "U2") (pin "29_1") (pinfunction "GND_29_1") (pintype "power_in"))
      (node (ref "U2") (pin "29_2") (pinfunction "GND_29_2") (pintype "power_in"))
      (node (ref "U2") (pin "29_3") (pinfunction "GND_29_3") (pintype "power_in"))
      (node (ref "U2") (pin "29_4") (pinfunction "GND_29_4") (pintype "power_in"))
      (node (ref "U2") (pin "29_5") (pinfunction "GND_29_5") (pintype "power_in"))
      (node (ref "U2") (pin "29_6") (pinfunction "GND_29_6") (pintype "power_in"))
      (node (ref "U2") (pin "29_7") (pinfunction "GND_29_7") (pintype "power_in"))
      (node (ref "U2") (pin "29_8") (pinfunction "GND_29_8") (pintype "power_in"))
      (node (ref "U2") (pin "29_9") (pinfunction "GND_29_9") (pintype "power_in"))
      (node (ref "U3") (pin "13") (pinfunction "GND_13") (pintype "power_in"))
      (node (ref "U4") (pin "1") (pinfunction "CTG_1") (pintype "power_in"))
      (node (ref "U4") (pin "4") (pinfunction "GND_4") (pintype "power_in"))
      (node (ref "U4") (pin "6") (pinfunction "QSTRT_6") (pintype "input"))
      (node (ref "U4") (pin "9") (pinfunction "EP_9") (pintype "power_in"))
      (node (ref "U5") (pin "2") (pinfunction "VSS_2") (pintype "power_in"))
    )
    (net (code "14") (name "GPIO8") (class "Default")
      (node (ref "R1") (pin "1") (pinfunction "1_1") (pintype "passive"))
      (node (ref "U2") (pin "10") (pinfunction "IO8_10") (pintype "bidirectional"))
    )
    (net (code "15") (name "I2C_PW") (class "Default")
      (node (ref "C1") (pin "1") (pinfunction "1_1") (pintype "passive"))
      (node (ref "C2") (pin "1") (pinfunction "1_1") (pintype "passive"))
      (node (ref "R1_PINH") (pin "2") (pinfunction "2_2") (pintype "passive"))
      (node (ref "R2_PINH") (pin "2") (pinfunction "2_2") (pintype "passive"))
      (node (ref "SENSOR2") (pin "2") (pinfunction "CSB_2") (pintype "input"))
      (node (ref "SENSOR2") (pin "6") (pinfunction "VDDIO_6") (pintype "power_in"))
      (node (ref "SENSOR2") (pin "8") (pinfunction "VDD_8") (pintype "power_in"))
      (node (ref "U2") (pin "17") (pinfunction "IO19_17") (pintype "bidirectional"))
    )
    (net (code "16") (name "INT_RTC") (class "Default")
      (node (ref "R1_PINH1") (pin "1") (pinfunction "1_1") (pintype "passive"))
      (node (ref "TP15") (pin "TP") (pinfunction "TP_TP") (pintype "input"))
      (node (ref "U2") (pin "8") (pinfunction "IO0_8") (pintype "bidirectional"))
      (node (ref "U3") (pin "3") (pinfunction "SQW/~{INT}_3") (pintype "output"))
    )
    (net (code "17") (name "IO{slash}BOOT") (class "Default")
      (node (ref "BOOT_BUTTON") (pin "3") (pinfunction "3_3") (pintype "passive"))
      (node (ref "BOOT_BUTTON") (pin "4") (pinfunction "4_4") (pintype "passive"))
      (node (ref "C6") (pin "1") (pinfunction "1_1") (pintype "passive"))
      (node (ref "R_BOOT") (pin "2") (pinfunction "2_2") (pintype "passive"))
      (node (ref "U2") (pin "15") (pinfunction "IO9_15") (pintype "bidirectional"))
    )
    (net (code "18") (name "IO{slash}CHANGE") (class "Default")
      (node (ref "C10") (pin "1") (pinfunction "1_1") (pintype "passive"))
      (node (ref "CHANGE_BUTTON") (pin "3") (pinfunction "3_3") (pintype "passive"))
      (node (ref "CHANGE_BUTTON") (pin "4") (pinfunction "4_4") (pintype "passive"))
      (node (ref "R_CHANGE") (pin "2") (pinfunction "2_2") (pintype "passive"))
      (node (ref "U2") (pin "23") (pinfunction "IO15_23") (pintype "bidirectional"))
    )
    (net (code "19") (name "MISO") (class "Default")
      (node (ref "D12") (pin "2") (pinfunction "2_2") (pintype "passive"))
      (node (ref "J4") (pin "P7") (pinfunction "DAT0_P7") (pintype "bidirectional"))
      (node (ref "R8") (pin "1") (pinfunction "1_1") (pintype "passive"))
      (node (ref "TP6") (pin "TP") (pinfunction "TP_TP") (pintype "input"))
      (node (ref "U1") (pin "2") (pinfunction "DO(IO1)_2") (pintype "bidirectional"))
      (node (ref "U2") (pin "27") (pinfunction "IO2_27") (pintype "bidirectional"))
    )
    (net (code "20") (name "MOSI") (class "Default")
      (node (ref "D11") (pin "2") (pinfunction "2_2") (pintype "passive"))
      (node (ref "J1") (pin "14") (pinfunction "14_14") (pintype "bidirectional"))
      (node (ref "J4") (pin "P3") (pinfunction "CMD_P3") (pintype "bidirectional"))
      (node (ref "R7") (pin "1") (pinfunction "1_1") (pintype "passive"))
      (node (ref "TP7") (pin "TP") (pinfunction "TP_TP") (pintype "input"))
      (node (ref "U1") (pin "5") (pinfunction "DI(IO0)_5") (pintype "bidirectional"))
      (node (ref "U2") (pin "7") (pinfunction "IO7_7") (pintype "bidirectional"))
    )
    (net (code "21") (name "Net-(CHG_LED-PadC)") (class "Default")
      (node (ref "CHG_LED") (pin "C") (pinfunction "C_C") (pintype "passive"))
      (node (ref "R1_BAT") (pin "2") (pinfunction "2_2") (pintype "passive"))
    )
    (net (code "22") (name "Net-(D2-CATHODE)") (class "Default")
      (node (ref "C1_BAT1") (pin "1") (pinfunction "1_1") (pintype "passive"))
      (node (ref "D2") (pin "1") (pinfunction "CATHODE_1") (pintype "bidirectional"))
      (node (ref "IC4") (pin "1") (pinfunction "VIN_1") (pintype "bidirectional"))
      (node (ref "IC4") (pin "3") (pinfunction "CE_3") (pintype "bidirectional"))
      (node (ref "Q1") (pin "2") (pinfunction "S_2") (pintype "bidirectional"))
    )
    (net (code "23") (name "Net-(D3-A)") (class "Default")
      (node (ref "C4") (pin "1") (pinfunction "1_1") (pintype "passive"))
      (node (ref "D3") (pin "2") (pinfunction "A_2") (pintype "bidirectional"))
      (node (ref "D4") (pin "1") (pinfunction "K_1") (pintype "bidirectional"))
    )
    (net (code "24") (name "Net-(D7-CATHODE)") (class "Default")
      (node (ref "D7") (pin "1") (pinfunction "CATHODE_1") (pintype "bidirectional"))
      (node (ref "R_CAPACITOR") (pin "2") (pinfunction "2_2") (pintype "passive"))
    )
    (net (code "25") (name "Net-(EPD_C1-Pad1)") (class "Default")
      (node (ref "EPD_C1") (pin "1") (pinfunction "1_1") (pintype "passive"))
      (node (ref "J1") (pin "4") (pinfunction "4_4") (pintype "bidirectional"))
    )
    (net (code "26") (name "Net-(EPD_C2-Pad1)") (class "Default")
      (node (ref "EPD_C2") (pin "1") (pinfunction "1_1") (pintype "passive"))
      (node (ref "J1") (pin "5") (pinfunction "5_5") (pintype "bidirectional"))
    )
    (net (code "27") (name "Net-(EPD_C6-Pad1)") (class "Default")
      (node (ref "EPD_C6") (pin "1") (pinfunction "1_1") (pintype "passive"))
      (node (ref "J1") (pin "18") (pinfunction "18_18") (pintype "bidirectional"))
    )
    (net (code "28") (name "Net-(EPD_C7-Pad1)") (class "Default")
      (node (ref "EPD_C7") (pin "1") (pinfunction "1_1") (pintype "passive"))
      (node (ref "J1") (pin "19") (pinfunction "19_19") (pintype "bidirectional"))
    )
    (net (code "29") (name "Net-(EPD_C8-Pad1)") (class "Default")
      (node (ref "EPD_C8") (pin "1") (pinfunction "1_1") (pintype "passive"))
      (node (ref "J1") (pin "20") (pinfunction "20_20") (pintype "bidirectional"))
    )
    (net (code "30") (name "Net-(EPD_C10-Pad1)") (class "Default")
      (node (ref "EPD_C10") (pin "1") (pinfunction "1_1") (pintype "passive"))
      (node (ref "J1") (pin "22") (pinfunction "22_22") (pintype "bidirectional"))
    )
    (net (code "31") (name "Net-(EPD_C12-Pad1)") (class "Default")
      (node (ref "EPD_C12") (pin "1") (pinfunction "1_1") (pintype "passive"))
      (node (ref "J1") (pin "24") (pinfunction "24_24") (pintype "bidirectional"))
    )
    (net (code "32") (name "Net-(IC1-CT)") (class "Default")
      (node (ref "C_DELAY") (pin "1") (pinfunction "1_1") (pintype "passive"))
      (node (ref "IC1") (pin "5") (pinfunction "CT_5") (pintype "bidirectional"))
    )
    (net (code "33") (name "Net-(J2-PadA5)") (class "Default")
      (node (ref "J2") (pin "A5") (pinfunction "A5_A5") (pintype "bidirectional"))
      (node (ref "R2-USB1") (pin "2") (pinfunction "2_2") (pintype "passive"))
    )
    (net (code "34") (name "Net-(J2-PadB5)") (class "Default")
      (node (ref "J2") (pin "B5") (pinfunction "B5_B5") (pintype "bidirectional"))
      (node (ref "R2-USB2") (pin "1") (pinfunction "1_1") (pintype "passive"))
    )
    (net (code "35") (name "Net-(U5-PROG)") (class "Default")
      (node (ref "R2_BAT") (pin "2") (pinfunction "2_2") (pintype "passive"))
      (node (ref "U5") (pin "5") (pinfunction "PROG_5") (pintype "input"))
    )
    (net (code "36") (name "Net-(U5-STAT)") (class "Default")
      (node (ref "R1_BAT") (pin "1") (pinfunction "1_1") (pintype "passive"))
      (node (ref "U5") (pin "1") (pinfunction "STAT_1") (pintype "output"))
    )
    (net (code "37") (name "PREVGH") (class "Default")
      (node (ref "D5") (pin "1") (pinfunction "K_1") (pintype "bidirectional"))
      (node (ref "EPD_C9") (pin "1") (pinfunction "1_1") (pintype "passive"))
      (node (ref "J1") (pin "21") (pinfunction "21_21") (pintype "bidirectional"))
    )
    (net (code "38") (name "PREVGL") (class "Default")
      (node (ref "D4") (pin "2") (pinfunction "A_2") (pintype "bidirectional"))
      (node (ref "EPD_C11") (pin "1") (pinfunction "1_1") (pintype "passive"))
      (node (ref "J1") (pin "23") (pinfunction "23_23") (pintype "bidirectional"))
    )
    (net (code "39") (name "RESE") (class "Default")
      (node (ref "J1") (pin "3") (pinfunction "3_3") (pintype "bidirectional"))
      (node (ref "Q3") (pin "2") (pinfunction "S_2") (pintype "bidirectional"))
      (node (ref "R3") (pin "2") (pinfunction "2_2") (pintype "passive"))
    )
    (net (code "40") (name "RESE'") (class "Default")
      (node (ref "R2") (pin "2") (pinfunction "2_2") (pintype "passive"))
      (node (ref "R3") (pin "1") (pinfunction "1_1") (pintype "passive"))
      (node (ref "SJ1") (pin "2") (pinfunction "2_2") (pintype "passive"))
    )
    (net (code "41") (name "RESET") (class "Default")
      (node (ref "C5") (pin "1") (pinfunction "1_1") (pintype "passive"))
      (node (ref "IC1") (pin "1") (pinfunction "VOUT_1") (pintype "bidirectional"))
      (node (ref "RESET_BUTTON") (pin "3") (pinfunction "3_3") (pintype "passive"))
      (node (ref "RESET_BUTTON") (pin "4") (pinfunction "4_4") (pintype "passive"))
      (node (ref "R_RESET") (pin "2") (pinfunction "2_2") (pintype "passive"))
      (node (ref "U2") (pin "3") (pinfunction "EN_3") (pintype "input"))
    )
    (net (code "42") (name "RTC_RST") (class "Default")
      (node (ref "U2") (pin "16") (pinfunction "IO18_16") (pintype "bidirectional"))
      (node (ref "U3") (pin "4") (pinfunction "~{RST}_4") (pintype "input"))
    )
    (net (code "43") (name "RX") (class "Default")
      (node (ref "TP2") (pin "TP") (pinfunction "TP_TP") (pintype "input"))
      (node (ref "U2") (pin "24") (pinfunction "RXD0/GPIO17_24") (pintype "bidirectional"))
    )
    (net (code "44") (name "SCK") (class "Default")
      (node (ref "D10") (pin "2") (pinfunction "2_2") (pintype "passive"))
      (node (ref "J1") (pin "13") (pinfunction "13_13") (pintype "bidirectional"))
      (node (ref "J4") (pin "P5") (pinfunction "CLK_P5") (pintype "bidirectional"))
      (node (ref "R6") (pin "1") (pinfunction "1_1") (pintype "passive"))
      (node (ref "TP8") (pin "TP") (pinfunction "TP_TP") (pintype "input"))
      (node (ref "U1") (pin "6") (pinfunction "CLK_6") (pintype "input"))
      (node (ref "U2") (pin "6") (pinfunction "IO6_6") (pintype "bidirectional"))
    )
    (net (code "45") (name "SCL") (class "Default")
      (node (ref "J3") (pin "4") (pinfunction "4_4") (pintype "passive"))
      (node (ref "R2_PINH") (pin "1") (pinfunction "1_1") (pintype "passive"))
      (node (ref "SENSOR2") (pin "4") (pinfunction "SCK_4") (pintype "input"))
      (node (ref "U2") (pin "20") (pinfunction "IO22_20") (pintype "bidirectional"))
      (node (ref "U3") (pin "16") (pinfunction "SCL_16") (pintype "input"))
      (node (ref "U4") (pin "7") (pinfunction "SCL_7") (pintype "input"))
    )
    (net (code "46") (name "SDA") (class "Default")
      (node (ref "J3") (pin "3") (pinfunction "3_3") (pintype "passive"))
      (node (ref "R1_PINH") (pin "1") (pinfunction "1_1") (pintype "passive"))
      (node (ref "SENSOR2") (pin "3") (pinfunction "SDI_3") (pintype "bidirectional"))
      (node (ref "U2") (pin "19") (pinfunction "IO21_19") (pintype "bidirectional"))
      (node (ref "U3") (pin "15") (pinfunction "SDA_15") (pintype "bidirectional"))
      (node (ref "U4") (pin "8") (pinfunction "SDA_8") (pintype "bidirectional"))
    )
    (net (code "47") (name "SRC") (class "Default")
      (node (ref "C4") (pin "2") (pinfunction "2_2") (pintype "passive"))
      (node (ref "D5") (pin "2") (pinfunction "A_2") (pintype "bidirectional"))
      (node (ref "L1") (pin "1") (pinfunction "1_1") (pintype "passive"))
      (node (ref "Q3") (pin "3") (pinfunction "D_3") (pintype "bidirectional"))
    )
    (net (code "48") (name "SS_SD") (class "Default")
      (node (ref "D8") (pin "2") (pinfunction "2_2") (pintype "passive"))
      (node (ref "J4") (pin "P2") (pinfunction "CD/DAT3_P2") (pintype "bidirectional"))
      (node (ref "R10") (pin "1") (pinfunction "1_1") (pintype "passive"))
      (node (ref "U2") (pin "4") (pinfunction "IO4_4") (pintype "bidirectional"))
    )
    (net (code "49") (name "TX") (class "Default")
      (node (ref "TP1") (pin "TP") (pinfunction "TP_TP") (pintype "input"))
      (node (ref "U2") (pin "25") (pinfunction "TXD0/GPIO16_25") (pintype "bidirectional"))
    )
    (net (code "50") (name "USB_D+") (class "Default")
      (node (ref "D1") (pin "1") (pinfunction "I/O1_1_1") (pintype "bidirectional"))
      (node (ref "U2") (pin "14") (pinfunction "IO13_14") (pintype "bidirectional"))
    )
    (net (code "51") (name "USB_D-") (class "Default")
      (node (ref "D1") (pin "3") (pinfunction "I/O2_1_3") (pintype "bidirectional"))
      (node (ref "U2") (pin "13") (pinfunction "IO12_13") (pintype "bidirectional"))
    )
    (net (code "52") (name "VBAT") (class "Default")
      (node (ref "C2_BAT") (pin "1") (pinfunction "1_1") (pintype "passive"))
      (node (ref "Q1") (pin "3") (pinfunction "D_3") (pintype "bidirectional"))
      (node (ref "TP3") (pin "TP") (pinfunction "TP_TP") (pintype "input"))
      (node (ref "U4") (pin "2") (pinfunction "CELL_2") (pintype "power_in"))
      (node (ref "U4") (pin "3") (pinfunction "VDD_3") (pintype "power_in"))
      (node (ref "U5") (pin "3") (pinfunction "VBAT_3") (pintype "power_in"))
    )
    (net (code "53") (name "VBUS") (class "Default")
      (node (ref "C1_BAT") (pin "1") (pinfunction "1_1") (pintype "passive"))
      (node (ref "C4_USB") (pin "1") (pinfunction "1_1") (pintype "passive"))
      (node (ref "C5_USB") (pin "1") (pinfunction "1_1") (pintype "passive"))
      (node (ref "CHG_LED") (pin "A") (pinfunction "A_A") (pintype "passive"))
      (node (ref "D1") (pin "5") (pinfunction "VBUS_5") (pintype "bidirectional"))
      (node (ref "D2") (pin "2") (pinfunction "ANODE_2") (pintype "bidirectional"))
      (node (ref "PFMF.050.1") (pin "2") (pinfunction "2_2") (pintype "passive"))
      (node (ref "Q1") (pin "1") (pinfunction "G_1") (pintype "bidirectional"))
      (node (ref "R1_PWRUSB") (pin "2") (pinfunction "2_2") (pintype "passive"))
      (node (ref "TP14") (pin "TP") (pinfunction "TP_TP") (pintype "input"))
      (node (ref "U5") (pin "4") (pinfunction "VIN_4") (pintype "power_in"))
    )
    (net (code "54") (name "VRTC") (class "Default")
      (node (ref "C10_SUPERCAP") (pin "2") (pinfunction "2_2") (pintype "passive"))
      (node (ref "C8") (pin "1") (pinfunction "1_1") (pintype "passive"))
      (node (ref "R_CAPACITOR") (pin "1") (pinfunction "1_1") (pintype "passive"))
      (node (ref "U3") (pin "14") (pinfunction "VBAT_14") (pintype "power_in"))
    )
    (net (code "55") (name "VUSB") (class "Default")
      (node (ref "J2") (pin "A4") (pinfunction "A4_A4") (pintype "bidirectional"))
      (node (ref "J2") (pin "A9") (pinfunction "A9_A9") (pintype "bidirectional"))
      (node (ref "J2") (pin "B4") (pinfunction "B4_B4") (pintype "bidirectional"))
      (node (ref "J2") (pin "B9") (pinfunction "B9_B9") (pintype "bidirectional"))
      (node (ref "PFMF.050.1") (pin "1") (pinfunction "1_1") (pintype "passive"))
    )
    (net (code "56") (name "unconnected-(IC1-NC-Pad4)") (class "Default")
      (node (ref "IC1") (pin "4") (pinfunction "NC_4") (pintype "no_connect"))
    )
    (net (code "57") (name "unconnected-(IC4-NC-Pad4)") (class "Default")
      (node (ref "IC4") (pin "4") (pinfunction "NC_4") (pintype "no_connect"))
    )
    (net (code "58") (name "unconnected-(J1-Pad1)") (class "Default")
      (node (ref "J1") (pin "1") (pinfunction "1_1") (pintype "bidirectional"))
    )
    (net (code "59") (name "unconnected-(J1-Pad6)") (class "Default")
      (node (ref "J1") (pin "6") (pinfunction "6_6") (pintype "bidirectional"))
    )
    (net (code "60") (name "unconnected-(J1-Pad7)") (class "Default")
      (node (ref "J1") (pin "7") (pinfunction "7_7") (pintype "bidirectional"))
    )
    (net (code "61") (name "unconnected-(J2-PadA8)") (class "Default")
      (node (ref "J2") (pin "A8") (pinfunction "A8_A8") (pintype "bidirectional"))
    )
    (net (code "62") (name "unconnected-(J2-PadB8)") (class "Default")
      (node (ref "J2") (pin "B8") (pinfunction "B8_B8") (pintype "bidirectional"))
    )
    (net (code "63") (name "unconnected-(J4-DAT1-PadP8)") (class "Default")
      (node (ref "J4") (pin "P8") (pinfunction "DAT1_P8") (pintype "bidirectional"))
    )
    (net (code "64") (name "unconnected-(J4-DAT2-PadP1)") (class "Default")
      (node (ref "J4") (pin "P1") (pinfunction "DAT2_P1") (pintype "bidirectional"))
    )
    (net (code "65") (name "unconnected-(J4-DETECTION_1-PadS1)") (class "Default")
      (node (ref "J4") (pin "S1") (pinfunction "DETECTION_1_S1") (pintype "bidirectional"))
    )
    (net (code "66") (name "unconnected-(J4-DETECTION_2-PadS2)") (class "Default")
      (node (ref "J4") (pin "S2") (pinfunction "DETECTION_2_S2") (pintype "bidirectional"))
    )
    (net (code "67") (name "unconnected-(U2-NC-Pad22)") (class "Default")
      (node (ref "U2") (pin "22") (pinfunction "NC_22") (pintype "no_connect"))
    )
    (net (code "68") (name "unconnected-(U4-~{ALERT}-Pad5)") (class "Default")
      (node (ref "U4") (pin "5") (pinfunction "~{ALERT}_5") (pintype "output"))
    )
  )
)
